# switch_button.net
KiCad netlist of a schematic drawn in EAGLE
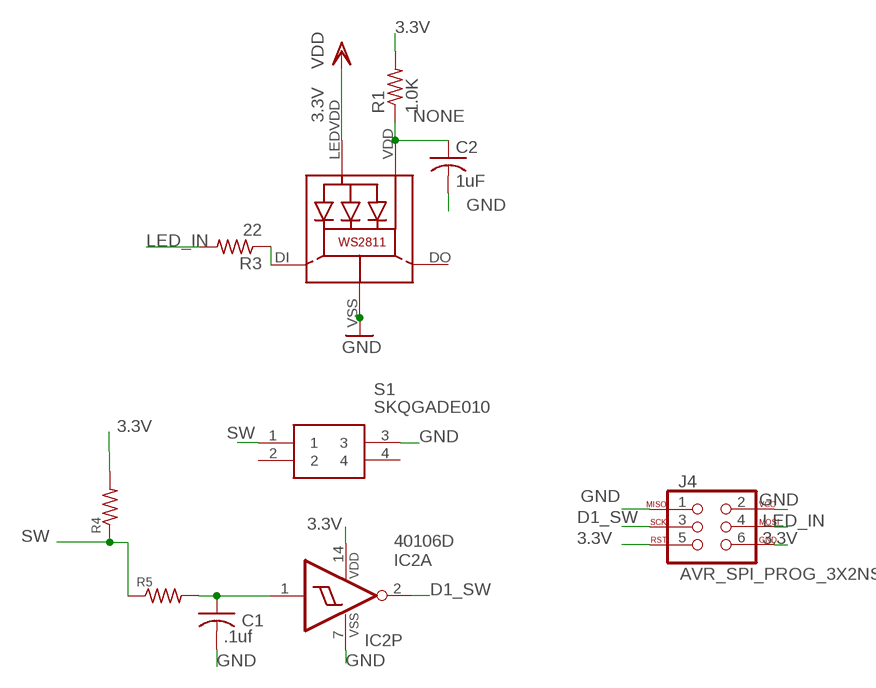
[diagram p0: schematic, sheet 1]

(export (version "E")
  (design (tool "Eeschema 10.0.6"))
  (components
    (comp (ref "C1")
      (value ".1uf")
      (footprint "eagle-import:ADAFRUIT_C1206K")
      (libsource (lib "eagle-import") (part "ADAFRUIT_C-USC1206K"))
    )
    (comp (ref "C2")
      (value "1uF")
      (footprint "eagle-import:C1206K")
      (libsource (lib "eagle-import") (part "C-USC1206K"))
    )
    (comp (ref "IC2")
      (value "40106D")
      (footprint "eagle-import:SO14")
      (libsource (lib "eagle-import") (part "40106D"))
    )
    (comp (ref "J4")
      (value "AVR_SPI_PROG_3X2NS")
      (footprint "eagle-import:2X3-NS")
      (libsource (lib "eagle-import") (part "AVR_SPI_PROG_3X2NS"))
    )
    (comp (ref "LED1")
      (value "WS28115050")
      (footprint "eagle-import:WS28115050")
      (libsource (lib "eagle-import") (part "WS28115050"))
    )
    (comp (ref "R1")
      (value "1.0K")
      (footprint "eagle-import:R1206FAB")
      (libsource (lib "eagle-import") (part "RES-US1206FAB"))
    )
    (comp (ref "R3")
      (value "22")
      (footprint "eagle-import:M1206")
      (libsource (lib "eagle-import") (part "R-US_M1206"))
    )
    (comp (ref "R4")
      (value "10k")
      (footprint "eagle-import:M1206")
      (libsource (lib "eagle-import") (part "adafruit_420_R-US_M1206"))
    )
    (comp (ref "R5")
      (value "10k")
      (footprint "eagle-import:M1206")
      (libsource (lib "eagle-import") (part "adafruit_420_R-US_M1206"))
    )
    (comp (ref "S1")
      (value "SKQGADE010")
      (footprint "eagle-import:SKQGAKE010")
      (fields (field (name "MOUSER_PART_NUMBER") "688-SKQGAD") (field (name "RS_PART_NUMBER") "7582067"))
      (libsource (lib "eagle-import") (part "SKQGADE010"))
    )
  )
  (nets
    (net (code "1") (name "/D1_SW") (class "Default")
      (node (ref "IC2") (pin "2") (pinfunction "O_2") (pintype "output"))
      (node (ref "J4") (pin "3") (pinfunction "3_3") (pintype "passive"))
    )
    (net (code "2") (name "/LED_IN") (class "Default")
      (node (ref "J4") (pin "4") (pinfunction "4_4") (pintype "passive"))
      (node (ref "R3") (pin "2") (pinfunction "2_2") (pintype "passive"))
    )
    (net (code "3") (name "/NONE") (class "Default")
      (node (ref "C2") (pin "1") (pinfunction "1_1") (pintype "passive"))
      (node (ref "LED1") (pin "VDD") (pinfunction "VDD_VDD") (pintype "power_in"))
      (node (ref "R1") (pin "1") (pinfunction "1_1") (pintype "passive"))
    )
    (net (code "4") (name "/SW") (class "Default")
      (node (ref "R4") (pin "1") (pinfunction "1_1") (pintype "passive"))
      (node (ref "R5") (pin "1") (pinfunction "1_1") (pintype "passive"))
      (node (ref "S1") (pin "1") (pinfunction "1_1") (pintype "bidirectional"))
    )
    (net (code "5") (name "GND") (class "Default")
      (node (ref "C1") (pin "2") (pinfunction "2_2") (pintype "passive"))
      (node (ref "C2") (pin "2") (pinfunction "2_2") (pintype "passive"))
      (node (ref "IC2") (pin "7") (pinfunction "VSS_7") (pintype "power_in"))
      (node (ref "J4") (pin "1") (pinfunction "1_1") (pintype "passive"))
      (node (ref "J4") (pin "2") (pinfunction "2_2") (pintype "passive"))
      (node (ref "LED1") (pin "VSS") (pinfunction "GND_VSS") (pintype "power_in"))
      (node (ref "S1") (pin "3") (pinfunction "3_3") (pintype "bidirectional"))
    )
    (net (code "6") (name "Net-(IC2A-I)") (class "Default")
      (node (ref "C1") (pin "1") (pinfunction "1_1") (pintype "passive"))
      (node (ref "IC2") (pin "1") (pinfunction "I_1") (pintype "input"))
      (node (ref "R5") (pin "2") (pinfunction "2_2") (pintype "passive"))
    )
    (net (code "7") (name "Net-(LED1-PadDI)") (class "Default")
      (node (ref "LED1") (pin "DI") (pinfunction "DI_DI") (pintype "input"))
      (node (ref "R3") (pin "1") (pinfunction "1_1") (pintype "passive"))
    )
    (net (code "8") (name "VDD") (class "Default")
      (node (ref "IC2") (pin "14") (pinfunction "VDD_14") (pintype "power_in"))
      (node (ref "J4") (pin "5") (pinfunction "5_5") (pintype "passive"))
      (node (ref "J4") (pin "6") (pinfunction "6_6") (pintype "passive"))
      (node (ref "LED1") (pin "LEDVDD") (pinfunction "LEDVDD_LEDVDD") (pintype "power_in"))
      (node (ref "R1") (pin "2") (pinfunction "2_2") (pintype "passive"))
      (node (ref "R4") (pin "2") (pinfunction "2_2") (pintype "passive"))
    )
    (net (code "9") (name "unconnected-(LED1-PadDO)") (class "Default")
      (node (ref "LED1") (pin "DO") (pinfunction "DO_DO") (pintype "output"))
    )
    (net (code "10") (name "unconnected-(S1-Pad2)") (class "Default")
      (node (ref "S1") (pin "2") (pinfunction "2_2") (pintype "bidirectional"))
    )
    (net (code "11") (name "unconnected-(S1-Pad4)") (class "Default")
      (node (ref "S1") (pin "4") (pinfunction "4_4") (pintype "bidirectional"))
    )
  )
)
